# Fastino-DIOT.net
KiCad netlist of a schematic drawn in Altium Designer
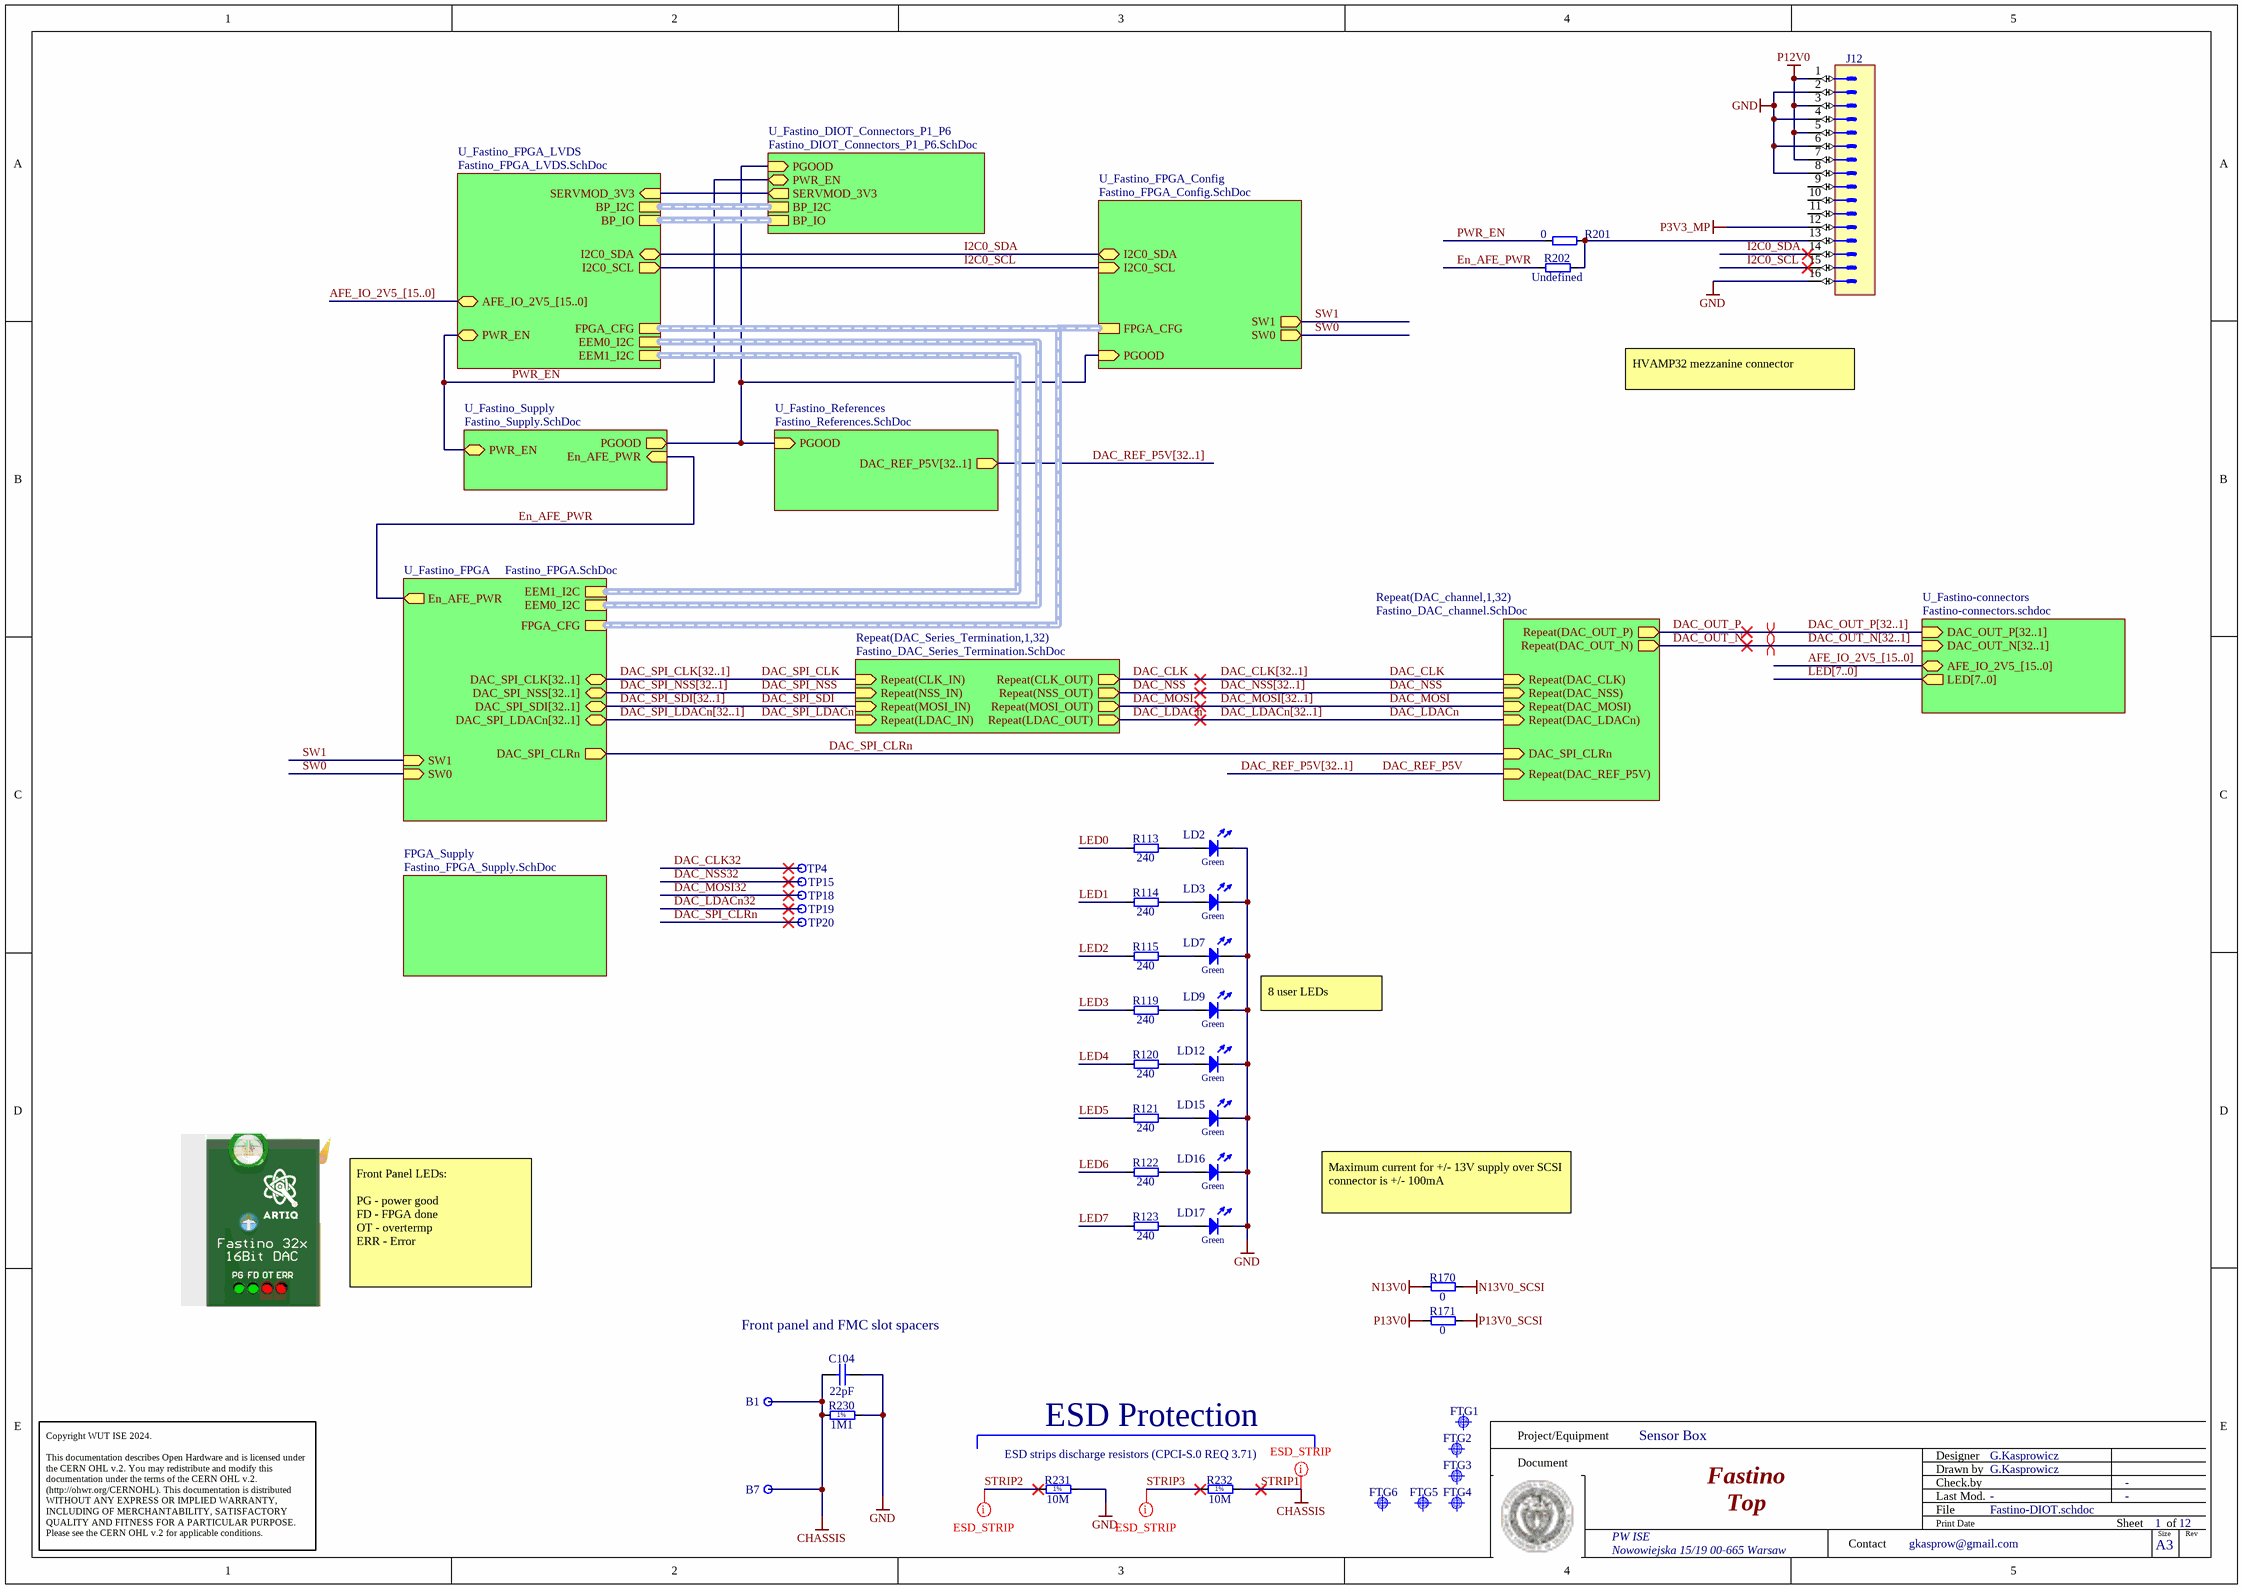
[diagram p0: Fastino-DIOT.schdoc]

(export (version "E")
  (design (tool "Eeschema 10.0.6"))
  (components
    (comp (ref "B1")
      (value "Plated Hole")
      (footprint "MTG270_500")
      (description "Single Terminal Socket")
      (fields (field (name "PART NUMBER") "PLATED_HOLE2.7_PAD5.0") (field (name "AUTHOR") "CERN DEM JMW"))
      (libsource (lib "Eletro-mechanical") (part "Single Terminal Socket"))
    )
    (comp (ref "B7")
      (value "Plated Hole")
      (footprint "MTG270_500")
      (description "Single Terminal Socket")
      (fields (field (name "PART NUMBER") "PLATED_HOLE2.7_PAD5.0") (field (name "AUTHOR") "CERN DEM JMW"))
      (libsource (lib "Eletro-mechanical") (part "Single Terminal Socket"))
    )
    (comp (ref "C104")
      (value "22pF")
      (footprint "CAPC1005X55N")
      (description "Non-polarised capacitor")
      (fields
        (field (name "PART NUMBER") "CC0402_22PF_50V_5%_C0G")
        (field (name "VOLTAGE") "50V")
        (field (name "AUTHOR") "CERN DEM JLC")
      )
      (libsource (lib "Capacitors") (part "Capacitor - non polarized"))
    )
    (comp (ref "FTG1")
      (value "Use only in PCB")
      (footprint "FIDUCIAL_TOP_S100-200")
      (description "Fiducial Target")
      (fields (field (name "PART NUMBER") "FIDUCIAL_TARGET_S100-200") (field (name "AUTHOR") "CERN DEM JLC"))
      (libsource (lib "Eletro-mechanical") (part "Fiducial Target"))
    )
    (comp (ref "FTG2")
      (value "Use only in PCB")
      (footprint "FIDUCIAL_TOP_S100-200")
      (description "Fiducial Target")
      (fields (field (name "PART NUMBER") "FIDUCIAL_TARGET_S100-200") (field (name "AUTHOR") "CERN DEM JLC"))
      (libsource (lib "Eletro-mechanical") (part "Fiducial Target"))
    )
    (comp (ref "FTG3")
      (value "Use only in PCB")
      (footprint "FIDUCIAL_TOP_S100-200")
      (description "Fiducial Target")
      (fields (field (name "PART NUMBER") "FIDUCIAL_TARGET_S100-200") (field (name "AUTHOR") "CERN DEM JLC"))
      (libsource (lib "Eletro-mechanical") (part "Fiducial Target"))
    )
    (comp (ref "FTG4")
      (value "Use only in PCB")
      (footprint "FIDUCIAL_TOP_S100-200")
      (description "Fiducial Target")
      (fields (field (name "PART NUMBER") "FIDUCIAL_TARGET_S100-200") (field (name "AUTHOR") "CERN DEM JLC"))
      (libsource (lib "Eletro-mechanical") (part "Fiducial Target"))
    )
    (comp (ref "FTG5")
      (value "Use only in PCB")
      (footprint "FIDUCIAL_TOP_S100-200")
      (description "Fiducial Target")
      (fields (field (name "PART NUMBER") "FIDUCIAL_TARGET_S100-200") (field (name "AUTHOR") "CERN DEM JLC"))
      (libsource (lib "Eletro-mechanical") (part "Fiducial Target"))
    )
    (comp (ref "FTG6")
      (value "Use only in PCB")
      (footprint "FIDUCIAL_TOP_S100-200")
      (description "Fiducial Target")
      (fields (field (name "PART NUMBER") "FIDUCIAL_TARGET_S100-200") (field (name "AUTHOR") "CERN DEM JLC"))
      (libsource (lib "Eletro-mechanical") (part "Fiducial Target"))
    )
    (comp (ref "J12")
      (value "Header 16")
      (footprint "3M_N2516-6002RB")
      (description "Connector 16 Male")
      (fields
        (field (name "PART NUMBER") "3M_N2516-6002RB")
        (field (name "MANUFACTURER") "3M")
        (field (name "AUTHOR") "CERN DEM JLC")
      )
      (libsource (lib "Connectors") (part "Connector 16 Male"))
    )
    (comp (ref "LD2")
      (value "Green")
      (footprint "LED_AVAGO_HSME-C120")
      (description "LED Green 1C 2A")
      (fields
        (field (name "PART NUMBER") "LED_AVAGO_HSME-C120")
        (field (name "MANUFACTURER") "AVAGO TECHNOLOGIES")
        (field (name "AUTHOR") "CERN DEM JMW")
      )
      (libsource (lib "ICs And Semiconductors") (part "LED Green 1C 2A"))
    )
    (comp (ref "LD3")
      (value "Green")
      (footprint "LED_AVAGO_HSME-C120")
      (description "LED Green 1C 2A")
      (fields
        (field (name "PART NUMBER") "LED_AVAGO_HSME-C120")
        (field (name "MANUFACTURER") "AVAGO TECHNOLOGIES")
        (field (name "AUTHOR") "CERN DEM JMW")
      )
      (libsource (lib "ICs And Semiconductors") (part "LED Green 1C 2A"))
    )
    (comp (ref "LD7")
      (value "Green")
      (footprint "LED_AVAGO_HSME-C120")
      (description "LED Green 1C 2A")
      (fields
        (field (name "PART NUMBER") "LED_AVAGO_HSME-C120")
        (field (name "MANUFACTURER") "AVAGO TECHNOLOGIES")
        (field (name "AUTHOR") "CERN DEM JMW")
      )
      (libsource (lib "ICs And Semiconductors") (part "LED Green 1C 2A"))
    )
    (comp (ref "LD9")
      (value "Green")
      (footprint "LED_AVAGO_HSME-C120")
      (description "LED Green 1C 2A")
      (fields
        (field (name "PART NUMBER") "LED_AVAGO_HSME-C120")
        (field (name "MANUFACTURER") "AVAGO TECHNOLOGIES")
        (field (name "AUTHOR") "CERN DEM JMW")
      )
      (libsource (lib "ICs And Semiconductors") (part "LED Green 1C 2A"))
    )
    (comp (ref "LD12")
      (value "Green")
      (footprint "LED_AVAGO_HSME-C120")
      (description "LED Green 1C 2A")
      (fields
        (field (name "PART NUMBER") "LED_AVAGO_HSME-C120")
        (field (name "MANUFACTURER") "AVAGO TECHNOLOGIES")
        (field (name "AUTHOR") "CERN DEM JMW")
      )
      (libsource (lib "ICs And Semiconductors") (part "LED Green 1C 2A"))
    )
    (comp (ref "LD15")
      (value "Green")
      (footprint "LED_AVAGO_HSME-C120")
      (description "LED Green 1C 2A")
      (fields
        (field (name "PART NUMBER") "LED_AVAGO_HSME-C120")
        (field (name "MANUFACTURER") "AVAGO TECHNOLOGIES")
        (field (name "AUTHOR") "CERN DEM JMW")
      )
      (libsource (lib "ICs And Semiconductors") (part "LED Green 1C 2A"))
    )
    (comp (ref "LD16")
      (value "Green")
      (footprint "LED_AVAGO_HSME-C120")
      (description "LED Green 1C 2A")
      (fields
        (field (name "PART NUMBER") "LED_AVAGO_HSME-C120")
        (field (name "MANUFACTURER") "AVAGO TECHNOLOGIES")
        (field (name "AUTHOR") "CERN DEM JMW")
      )
      (libsource (lib "ICs And Semiconductors") (part "LED Green 1C 2A"))
    )
    (comp (ref "LD17")
      (value "Green")
      (footprint "LED_AVAGO_HSME-C120")
      (description "LED Green 1C 2A")
      (fields
        (field (name "PART NUMBER") "LED_AVAGO_HSME-C120")
        (field (name "MANUFACTURER") "AVAGO TECHNOLOGIES")
        (field (name "AUTHOR") "CERN DEM JMW")
      )
      (libsource (lib "ICs And Semiconductors") (part "LED Green 1C 2A"))
    )
    (comp (ref "R113")
      (value "240")
      (footprint "RESC1005X40N")
      (description "Resistor - 1%")
      (fields
        (field (name "PART NUMBER") "R0402_240R_1%_0.0625W_100PPM")
        (field (name "POWER") "0.0625W")
        (field (name "AUTHOR") "CERN DEM JLC")
      )
      (libsource (lib "") (part "Resistor - 1%_1"))
    )
    (comp (ref "R114")
      (value "240")
      (footprint "RESC1005X40N")
      (description "Resistor - 1%")
      (fields
        (field (name "PART NUMBER") "R0402_240R_1%_0.0625W_100PPM")
        (field (name "POWER") "0.0625W")
        (field (name "AUTHOR") "CERN DEM JLC")
      )
      (libsource (lib "") (part "Resistor - 1%_1"))
    )
    (comp (ref "R115")
      (value "240")
      (footprint "RESC1005X40N")
      (description "Resistor - 1%")
      (fields
        (field (name "PART NUMBER") "R0402_240R_1%_0.0625W_100PPM")
        (field (name "POWER") "0.0625W")
        (field (name "AUTHOR") "CERN DEM JLC")
      )
      (libsource (lib "") (part "Resistor - 1%_1"))
    )
    (comp (ref "R119")
      (value "240")
      (footprint "RESC1005X40N")
      (description "Resistor - 1%")
      (fields
        (field (name "PART NUMBER") "R0402_240R_1%_0.0625W_100PPM")
        (field (name "POWER") "0.0625W")
        (field (name "AUTHOR") "CERN DEM JLC")
      )
      (libsource (lib "") (part "Resistor - 1%_1"))
    )
    (comp (ref "R120")
      (value "240")
      (footprint "RESC1005X40N")
      (description "Resistor - 1%")
      (fields
        (field (name "PART NUMBER") "R0402_240R_1%_0.0625W_100PPM")
        (field (name "POWER") "0.0625W")
        (field (name "AUTHOR") "CERN DEM JLC")
      )
      (libsource (lib "") (part "Resistor - 1%_1"))
    )
    (comp (ref "R121")
      (value "240")
      (footprint "RESC1005X40N")
      (description "Resistor - 1%")
      (fields
        (field (name "PART NUMBER") "R0402_240R_1%_0.0625W_100PPM")
        (field (name "POWER") "0.0625W")
        (field (name "AUTHOR") "CERN DEM JLC")
      )
      (libsource (lib "") (part "Resistor - 1%_1"))
    )
    (comp (ref "R122")
      (value "240")
      (footprint "RESC1005X40N")
      (description "Resistor - 1%")
      (fields
        (field (name "PART NUMBER") "R0402_240R_1%_0.0625W_100PPM")
        (field (name "POWER") "0.0625W")
        (field (name "AUTHOR") "CERN DEM JLC")
      )
      (libsource (lib "") (part "Resistor - 1%_1"))
    )
    (comp (ref "R123")
      (value "240")
      (footprint "RESC1005X40N")
      (description "Resistor - 1%")
      (fields
        (field (name "PART NUMBER") "R0402_240R_1%_0.0625W_100PPM")
        (field (name "POWER") "0.0625W")
        (field (name "AUTHOR") "CERN DEM JLC")
      )
      (libsource (lib "") (part "Resistor - 1%_1"))
    )
    (comp (ref "R170")
      (value "0")
      (footprint "RESC3216X65N")
      (description "Resistor")
      (fields
        (field (name "PART NUMBER") "R1206_0R_JUMPER")
        (field (name "MANUFACTURER") "GENERIC")
        (field (name "AUTHOR") "CERN DEM JLC")
      )
      (libsource (lib "Resistors") (part "Resistor"))
    )
    (comp (ref "R171")
      (value "0")
      (footprint "RESC3216X65N")
      (description "Resistor")
      (fields
        (field (name "PART NUMBER") "R1206_0R_JUMPER")
        (field (name "MANUFACTURER") "GENERIC")
        (field (name "AUTHOR") "CERN DEM JLC")
      )
      (libsource (lib "Resistors") (part "Resistor"))
    )
    (comp (ref "R201")
      (value "0")
      (footprint "RESC1005X40N")
      (description "Resistor")
      (fields
        (field (name "PART NUMBER") "R0402_0R_JUMPER")
        (field (name "MANUFACTURER") "GENERIC")
        (field (name "AUTHOR") "CERN DEM JLC")
      )
      (libsource (lib "Resistors") (part "Resistor"))
    )
    (comp (ref "R202")
      (value "Undefined")
      (footprint "RESC1608X55N")
      (description "Resistor")
      (fields (field (name "PART NUMBER") "R0603_NO-VALUE") (field (name "AUTHOR") "CERN DEM JLC"))
      (libsource (lib "Resistors") (part "Resistor"))
    )
    (comp (ref "R230")
      (value "1M1")
      (footprint "RESC2012X60N")
      (description "Resistor - 1%")
      (fields
        (field (name "PART NUMBER") "R0805_1M1_1%_0.125W_100PPM")
        (field (name "POWER") "0.125W")
        (field (name "AUTHOR") "CERN DEM JLC")
      )
      (libsource (lib "Resistors") (part "Resistor - 1%"))
    )
    (comp (ref "R231")
      (value "10M")
      (footprint "RESC2113X55N")
      (description "Resistor - 1%")
      (fields
        (field (name "PART NUMBER") "R0805_10M_1%_0.125W_100PPM_VISHAY_CRCW e3")
        (field (name "POWER") "0.125W")
        (field (name "AUTHOR") "CERN DEM BC")
      )
      (libsource (lib "Resistors") (part "Resistor - 1%"))
    )
    (comp (ref "R232")
      (value "10M")
      (footprint "RESC2113X55N")
      (description "Resistor - 1%")
      (fields
        (field (name "PART NUMBER") "R0805_10M_1%_0.125W_100PPM_VISHAY_CRCW e3")
        (field (name "POWER") "0.125W")
        (field (name "AUTHOR") "CERN DEM BC")
      )
      (libsource (lib "Resistors") (part "Resistor - 1%"))
    )
    (comp (ref "TP4")
      (value "Test Point")
      (footprint "TPS127")
      (fields (field (name "PART NUMBER") "SMD_PAD_1.27X1.27MM") (field (name "AUTHOR") "CERN DEM JLC"))
      (libsource (lib "Eletro-mechanical") (part "Test Point"))
    )
    (comp (ref "TP15")
      (value "Test Point")
      (footprint "TPS127")
      (fields (field (name "PART NUMBER") "SMD_PAD_1.27X1.27MM") (field (name "AUTHOR") "CERN DEM JLC"))
      (libsource (lib "Eletro-mechanical") (part "Test Point"))
    )
    (comp (ref "TP18")
      (value "Test Point")
      (footprint "TPS127")
      (fields (field (name "PART NUMBER") "SMD_PAD_1.27X1.27MM") (field (name "AUTHOR") "CERN DEM JLC"))
      (libsource (lib "Eletro-mechanical") (part "Test Point"))
    )
    (comp (ref "TP19")
      (value "Test Point")
      (footprint "TPS127")
      (fields (field (name "PART NUMBER") "SMD_PAD_1.27X1.27MM") (field (name "AUTHOR") "CERN DEM JLC"))
      (libsource (lib "Eletro-mechanical") (part "Test Point"))
    )
    (comp (ref "TP20")
      (value "Test Point")
      (footprint "TPS127")
      (fields (field (name "PART NUMBER") "SMD_PAD_1.27X1.27MM") (field (name "AUTHOR") "CERN DEM JLC"))
      (libsource (lib "Eletro-mechanical") (part "Test Point"))
    )
  )
  (nets
    (net (code "369") (name "/DAC_CLK32") (class "Default")
      (node (ref "TP4") (pin "1") (pinfunction "1_1") (pintype "bidirectional"))
    )
    (net (code "372") (name "/DAC_LDACn32") (class "Default")
      (node (ref "TP19") (pin "1") (pinfunction "1_1") (pintype "bidirectional"))
    )
    (net (code "375") (name "/DAC_MOSI32") (class "Default")
      (node (ref "TP18") (pin "1") (pinfunction "1_1") (pintype "bidirectional"))
    )
    (net (code "378") (name "/DAC_NSS32") (class "Default")
      (node (ref "TP15") (pin "1") (pinfunction "1_1") (pintype "bidirectional"))
    )
    (net (code "388") (name "/DAC_SPI_CLRn") (class "Default")
      (node (ref "TP20") (pin "1") (pinfunction "1_1") (pintype "bidirectional"))
    )
    (net (code "397") (name "/En_AFE_PWR") (class "Default")
      (node (ref "R202") (pin "1") (pinfunction "1_1") (pintype "passive"))
    )
    (net (code "399") (name "/I2C0_SCL") (class "Default")
      (node (ref "J12") (pin "15") (pinfunction "15_15") (pintype "bidirectional+no_connect"))
    )
    (net (code "400") (name "/I2C0_SDA") (class "Default")
      (node (ref "J12") (pin "14") (pinfunction "14_14") (pintype "bidirectional+no_connect"))
    )
    (net (code "401") (name "/LED0") (class "Default")
      (node (ref "R113") (pin "1") (pinfunction "1_1") (pintype "passive"))
    )
    (net (code "402") (name "/LED1") (class "Default")
      (node (ref "R114") (pin "1") (pinfunction "1_1") (pintype "passive"))
    )
    (net (code "403") (name "/LED2") (class "Default")
      (node (ref "R115") (pin "1") (pinfunction "1_1") (pintype "passive"))
    )
    (net (code "404") (name "/LED3") (class "Default")
      (node (ref "R119") (pin "1") (pinfunction "1_1") (pintype "passive"))
    )
    (net (code "405") (name "/LED4") (class "Default")
      (node (ref "R120") (pin "1") (pinfunction "1_1") (pintype "passive"))
    )
    (net (code "406") (name "/LED5") (class "Default")
      (node (ref "R121") (pin "1") (pinfunction "1_1") (pintype "passive"))
    )
    (net (code "407") (name "/LED6") (class "Default")
      (node (ref "R122") (pin "1") (pinfunction "1_1") (pintype "passive"))
    )
    (net (code "408") (name "/LED7") (class "Default")
      (node (ref "R123") (pin "1") (pinfunction "1_1") (pintype "passive"))
    )
    (net (code "411") (name "/PWR_EN") (class "Default")
      (node (ref "R201") (pin "2") (pinfunction "2_2") (pintype "passive"))
    )
    (net (code "414") (name "/STRIP2") (class "Default")
      (node (ref "R231") (pin "1") (pinfunction "1_1") (pintype "passive+no_connect"))
    )
    (net (code "415") (name "/STRIP3") (class "Default")
      (node (ref "R232") (pin "1") (pinfunction "1_1") (pintype "passive+no_connect"))
    )
    (net (code "418") (name "CHASSIS") (class "Default")
      (node (ref "B1") (pin "1") (pinfunction "1_1") (pintype "bidirectional"))
      (node (ref "B7") (pin "1") (pinfunction "1_1") (pintype "bidirectional"))
      (node (ref "C104") (pin "1") (pinfunction "1_1") (pintype "passive"))
      (node (ref "R230") (pin "1") (pinfunction "1_1") (pintype "passive"))
      (node (ref "R232") (pin "2") (pinfunction "2_2") (pintype "passive"))
    )
    (net (code "419") (name "GND") (class "Default")
      (node (ref "C104") (pin "2") (pinfunction "2_2") (pintype "passive"))
      (node (ref "J12") (pin "16") (pinfunction "16_16") (pintype "bidirectional"))
      (node (ref "J12") (pin "2") (pinfunction "2_2") (pintype "bidirectional"))
      (node (ref "J12") (pin "4") (pinfunction "4_4") (pintype "bidirectional"))
      (node (ref "J12") (pin "6") (pinfunction "6_6") (pintype "bidirectional"))
      (node (ref "J12") (pin "8") (pinfunction "8_8") (pintype "bidirectional"))
      (node (ref "LD12") (pin "1") (pinfunction "C_1") (pintype "passive"))
      (node (ref "LD15") (pin "1") (pinfunction "C_1") (pintype "passive"))
      (node (ref "LD16") (pin "1") (pinfunction "C_1") (pintype "passive"))
      (node (ref "LD17") (pin "1") (pinfunction "C_1") (pintype "passive"))
      (node (ref "LD2") (pin "1") (pinfunction "C_1") (pintype "passive"))
      (node (ref "LD3") (pin "1") (pinfunction "C_1") (pintype "passive"))
      (node (ref "LD7") (pin "1") (pinfunction "C_1") (pintype "passive"))
      (node (ref "LD9") (pin "1") (pinfunction "C_1") (pintype "passive"))
      (node (ref "R230") (pin "2") (pinfunction "2_2") (pintype "passive"))
      (node (ref "R231") (pin "2") (pinfunction "2_2") (pintype "passive"))
    )
    (net (code "420") (name "N13V0") (class "Default")
      (node (ref "R170") (pin "1") (pinfunction "1_1") (pintype "passive"))
    )
    (net (code "421") (name "N13V0_SCSI") (class "Default")
      (node (ref "R170") (pin "2") (pinfunction "2_2") (pintype "passive"))
    )
    (net (code "422") (name "Net-(J12-Pad13)") (class "Default")
      (node (ref "J12") (pin "13") (pinfunction "13_13") (pintype "bidirectional"))
      (node (ref "R201") (pin "1") (pinfunction "1_1") (pintype "passive"))
      (node (ref "R202") (pin "2") (pinfunction "2_2") (pintype "passive"))
    )
    (net (code "423") (name "Net-(LD2-A)") (class "Default")
      (node (ref "LD2") (pin "2") (pinfunction "A_2") (pintype "passive"))
      (node (ref "R113") (pin "2") (pinfunction "2_2") (pintype "passive"))
    )
    (net (code "424") (name "Net-(LD3-A)") (class "Default")
      (node (ref "LD3") (pin "2") (pinfunction "A_2") (pintype "passive"))
      (node (ref "R114") (pin "2") (pinfunction "2_2") (pintype "passive"))
    )
    (net (code "425") (name "Net-(LD7-A)") (class "Default")
      (node (ref "LD7") (pin "2") (pinfunction "A_2") (pintype "passive"))
      (node (ref "R115") (pin "2") (pinfunction "2_2") (pintype "passive"))
    )
    (net (code "426") (name "Net-(LD9-A)") (class "Default")
      (node (ref "LD9") (pin "2") (pinfunction "A_2") (pintype "passive"))
      (node (ref "R119") (pin "2") (pinfunction "2_2") (pintype "passive"))
    )
    (net (code "427") (name "Net-(LD12-A)") (class "Default")
      (node (ref "LD12") (pin "2") (pinfunction "A_2") (pintype "passive"))
      (node (ref "R120") (pin "2") (pinfunction "2_2") (pintype "passive"))
    )
    (net (code "428") (name "Net-(LD15-A)") (class "Default")
      (node (ref "LD15") (pin "2") (pinfunction "A_2") (pintype "passive"))
      (node (ref "R121") (pin "2") (pinfunction "2_2") (pintype "passive"))
    )
    (net (code "429") (name "Net-(LD16-A)") (class "Default")
      (node (ref "LD16") (pin "2") (pinfunction "A_2") (pintype "passive"))
      (node (ref "R122") (pin "2") (pinfunction "2_2") (pintype "passive"))
    )
    (net (code "430") (name "Net-(LD17-A)") (class "Default")
      (node (ref "LD17") (pin "2") (pinfunction "A_2") (pintype "passive"))
      (node (ref "R123") (pin "2") (pinfunction "2_2") (pintype "passive"))
    )
    (net (code "431") (name "P3V3_MP") (class "Default")
      (node (ref "J12") (pin "12") (pinfunction "12_12") (pintype "bidirectional"))
    )
    (net (code "432") (name "P12V0") (class "Default")
      (node (ref "J12") (pin "1") (pinfunction "1_1") (pintype "bidirectional"))
      (node (ref "J12") (pin "3") (pinfunction "3_3") (pintype "bidirectional"))
      (node (ref "J12") (pin "5") (pinfunction "5_5") (pintype "bidirectional"))
      (node (ref "J12") (pin "7") (pinfunction "7_7") (pintype "bidirectional"))
    )
    (net (code "433") (name "P13V0") (class "Default")
      (node (ref "R171") (pin "1") (pinfunction "1_1") (pintype "passive"))
    )
    (net (code "434") (name "P13V0_SCSI") (class "Default")
      (node (ref "R171") (pin "2") (pinfunction "2_2") (pintype "passive"))
    )
    (net (code "435") (name "unconnected-(J12-Pad9)") (class "Default")
      (node (ref "J12") (pin "9") (pinfunction "9_9") (pintype "bidirectional"))
    )
    (net (code "436") (name "unconnected-(J12-Pad10)") (class "Default")
      (node (ref "J12") (pin "10") (pinfunction "10_10") (pintype "bidirectional"))
    )
    (net (code "437") (name "unconnected-(J12-Pad11)") (class "Default")
      (node (ref "J12") (pin "11") (pinfunction "11_11") (pintype "bidirectional"))
    )
  )
)
